# car1.net
KiCad netlist of a schematic drawn in EAGLE
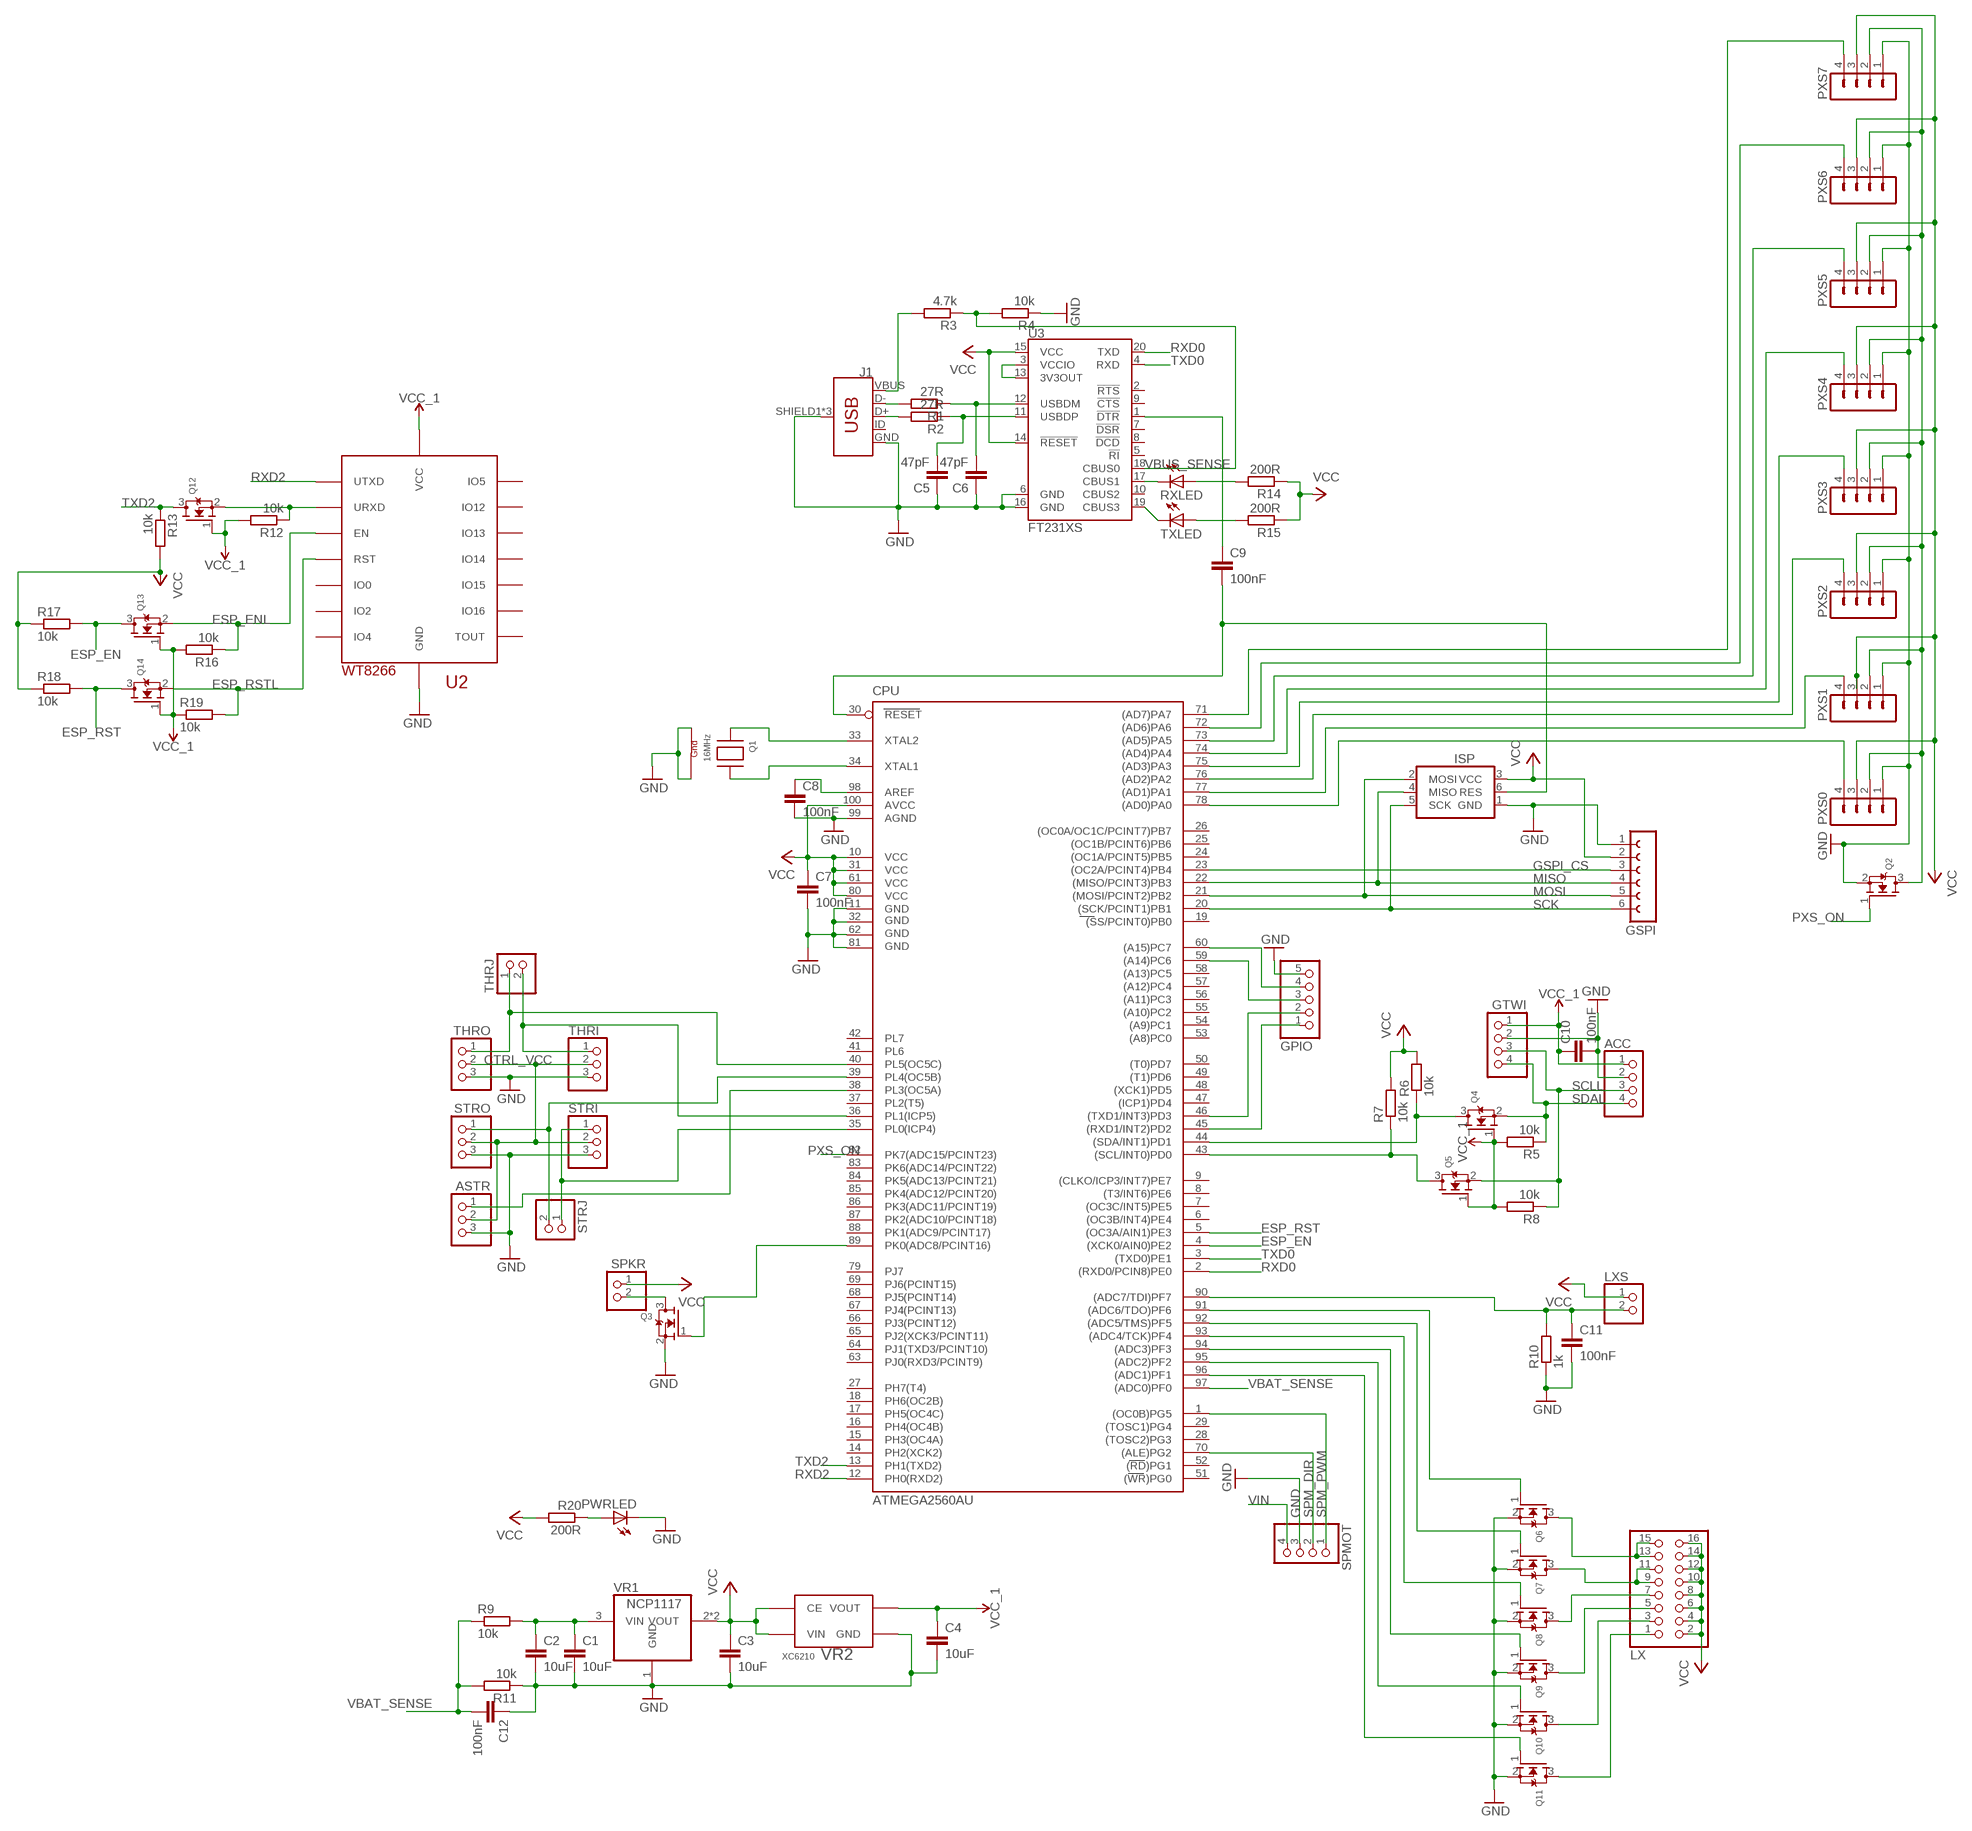
[diagram p0: schematic, sheet 1]

(export (version "E")
  (design (tool "Eeschema 10.0.6"))
  (components
    (comp (ref "ACC")
      (value "PINHD-1X4")
      (footprint "eagle-import:1X04")
      (libsource (lib "eagle-import") (part "PINHD-1X4"))
    )
    (comp (ref "ASTR")
      (value "PINHD-1X3")
      (footprint "eagle-import:1X03")
      (libsource (lib "eagle-import") (part "PINHD-1X3"))
    )
    (comp (ref "C1")
      (value "10uF")
      (footprint "eagle-import:C1206")
      (libsource (lib "eagle-import") (part "C-EUC1206"))
    )
    (comp (ref "C2")
      (value "10uF")
      (footprint "eagle-import:C1206")
      (libsource (lib "eagle-import") (part "C-EUC1206"))
    )
    (comp (ref "C3")
      (value "10uF")
      (footprint "eagle-import:C1206")
      (libsource (lib "eagle-import") (part "C-EUC1206"))
    )
    (comp (ref "C4")
      (value "10uF")
      (footprint "eagle-import:C1206")
      (libsource (lib "eagle-import") (part "C-EUC1206"))
    )
    (comp (ref "C5")
      (value "47pF")
      (footprint "eagle-import:C0603")
      (libsource (lib "eagle-import") (part "C-EUC0603"))
    )
    (comp (ref "C6")
      (value "47pF")
      (footprint "eagle-import:C0603")
      (libsource (lib "eagle-import") (part "C-EUC0603"))
    )
    (comp (ref "C7")
      (value "100nF")
      (footprint "eagle-import:C1206")
      (libsource (lib "eagle-import") (part "C-EUC1206"))
    )
    (comp (ref "C8")
      (value "100nF")
      (footprint "eagle-import:C1206")
      (libsource (lib "eagle-import") (part "C-EUC1206"))
    )
    (comp (ref "C9")
      (value "100nF")
      (footprint "eagle-import:C1206")
      (libsource (lib "eagle-import") (part "C-EUC1206"))
    )
    (comp (ref "C10")
      (value "100nF")
      (footprint "eagle-import:C1206")
      (libsource (lib "eagle-import") (part "C-EUC1206"))
    )
    (comp (ref "C11")
      (value "100nF")
      (footprint "eagle-import:C1206")
      (libsource (lib "eagle-import") (part "C-EUC1206"))
    )
    (comp (ref "C12")
      (value "100nF")
      (footprint "eagle-import:C1206")
      (libsource (lib "eagle-import") (part "C-EUC1206"))
    )
    (comp (ref "CPU")
      (value "ATMEGA2560AU")
      (footprint "eagle-import:TQFP100")
      (libsource (lib "eagle-import") (part "ATMEGA2560AU"))
    )
    (comp (ref "GPIO")
      (value "PINHD-1X5")
      (footprint "eagle-import:1X05")
      (libsource (lib "eagle-import") (part "PINHD-1X5"))
    )
    (comp (ref "GSPI")
      (value "FE06W")
      (footprint "eagle-import:FE06W")
      (libsource (lib "eagle-import") (part "FE06W"))
    )
    (comp (ref "GTWI")
      (value "PINHD-1X4/90")
      (footprint "eagle-import:1X04_90")
      (libsource (lib "eagle-import") (part "PINHD-1X4/90"))
    )
    (comp (ref "ISP")
      (value "ISP")
      (footprint "eagle-import:ISP")
      (libsource (lib "eagle-import") (part "ISP"))
    )
    (comp (ref "J1")
      (value "USB_MICRO-B_FEMALE-SMT")
      (footprint "eagle-import:USB-B-MICRO-SMD")
      (libsource (lib "eagle-import") (part "USB_MICRO-B_FEMALE-SMT"))
    )
    (comp (ref "LX")
      (value "PINHD-2X8")
      (footprint "eagle-import:2X08")
      (libsource (lib "eagle-import") (part "PINHD-2X8"))
    )
    (comp (ref "LXS")
      (value "PINHD-1X2")
      (footprint "eagle-import:1X02")
      (libsource (lib "eagle-import") (part "PINHD-1X2"))
    )
    (comp (ref "PWRLED")
      (value "LEDCHIP-LED0603")
      (footprint "eagle-import:CHIP-LED0603")
      (libsource (lib "eagle-import") (part "LEDCHIP-LED0603"))
    )
    (comp (ref "PXS0")
      (value "MA04-1")
      (footprint "eagle-import:MA04-1")
      (libsource (lib "eagle-import") (part "MA04-1"))
    )
    (comp (ref "PXS1")
      (value "MA04-1")
      (footprint "eagle-import:MA04-1")
      (libsource (lib "eagle-import") (part "MA04-1"))
    )
    (comp (ref "PXS2")
      (value "MA04-1")
      (footprint "eagle-import:MA04-1")
      (libsource (lib "eagle-import") (part "MA04-1"))
    )
    (comp (ref "PXS3")
      (value "MA04-1")
      (footprint "eagle-import:MA04-1")
      (libsource (lib "eagle-import") (part "MA04-1"))
    )
    (comp (ref "PXS4")
      (value "MA04-1")
      (footprint "eagle-import:MA04-1")
      (libsource (lib "eagle-import") (part "MA04-1"))
    )
    (comp (ref "PXS5")
      (value "MA04-1")
      (footprint "eagle-import:MA04-1")
      (libsource (lib "eagle-import") (part "MA04-1"))
    )
    (comp (ref "PXS6")
      (value "MA04-1")
      (footprint "eagle-import:MA04-1")
      (libsource (lib "eagle-import") (part "MA04-1"))
    )
    (comp (ref "PXS7")
      (value "MA04-1")
      (footprint "eagle-import:MA04-1")
      (libsource (lib "eagle-import") (part "MA04-1"))
    )
    (comp (ref "Q1")
      (value "16MHz")
      (footprint "eagle-import:NX3225")
      (libsource (lib "eagle-import") (part "XTAL-4-3225"))
    )
    (comp (ref "Q2")
      (value "MOSFET-NREFLOW")
      (footprint "eagle-import:SOT23")
      (libsource (lib "eagle-import") (part "MOSFET-NREFLOW"))
    )
    (comp (ref "Q3")
      (value "MOSFET-NREFLOW")
      (footprint "eagle-import:SOT23")
      (libsource (lib "eagle-import") (part "MOSFET-NREFLOW"))
    )
    (comp (ref "Q4")
      (value "MOSFET-NREFLOW")
      (footprint "eagle-import:SOT23")
      (libsource (lib "eagle-import") (part "MOSFET-NREFLOW"))
    )
    (comp (ref "Q5")
      (value "MOSFET-NREFLOW")
      (footprint "eagle-import:SOT23")
      (libsource (lib "eagle-import") (part "MOSFET-NREFLOW"))
    )
    (comp (ref "Q6")
      (value "MOSFET-NREFLOW")
      (footprint "eagle-import:SOT23")
      (libsource (lib "eagle-import") (part "MOSFET-NREFLOW"))
    )
    (comp (ref "Q7")
      (value "MOSFET-NREFLOW")
      (footprint "eagle-import:SOT23")
      (libsource (lib "eagle-import") (part "MOSFET-NREFLOW"))
    )
    (comp (ref "Q8")
      (value "MOSFET-NREFLOW")
      (footprint "eagle-import:SOT23")
      (libsource (lib "eagle-import") (part "MOSFET-NREFLOW"))
    )
    (comp (ref "Q9")
      (value "MOSFET-NREFLOW")
      (footprint "eagle-import:SOT23")
      (libsource (lib "eagle-import") (part "MOSFET-NREFLOW"))
    )
    (comp (ref "Q10")
      (value "MOSFET-NREFLOW")
      (footprint "eagle-import:SOT23")
      (libsource (lib "eagle-import") (part "MOSFET-NREFLOW"))
    )
    (comp (ref "Q11")
      (value "MOSFET-NREFLOW")
      (footprint "eagle-import:SOT23")
      (libsource (lib "eagle-import") (part "MOSFET-NREFLOW"))
    )
    (comp (ref "Q12")
      (value "MOSFET-NREFLOW")
      (footprint "eagle-import:SOT23")
      (libsource (lib "eagle-import") (part "MOSFET-NREFLOW"))
    )
    (comp (ref "Q13")
      (value "MOSFET-NREFLOW")
      (footprint "eagle-import:SOT23")
      (libsource (lib "eagle-import") (part "MOSFET-NREFLOW"))
    )
    (comp (ref "Q14")
      (value "MOSFET-NREFLOW")
      (footprint "eagle-import:SOT23")
      (libsource (lib "eagle-import") (part "MOSFET-NREFLOW"))
    )
    (comp (ref "R1")
      (value "27R")
      (footprint "eagle-import:R0603")
      (libsource (lib "eagle-import") (part "R-EU_R0603"))
    )
    (comp (ref "R2")
      (value "27R")
      (footprint "eagle-import:R0603")
      (libsource (lib "eagle-import") (part "R-EU_R0603"))
    )
    (comp (ref "R3")
      (value "4.7k")
      (footprint "eagle-import:R0603")
      (libsource (lib "eagle-import") (part "R-EU_R0603"))
    )
    (comp (ref "R4")
      (value "10k")
      (footprint "eagle-import:R0603")
      (libsource (lib "eagle-import") (part "R-EU_R0603"))
    )
    (comp (ref "R5")
      (value "10k")
      (footprint "eagle-import:R0603")
      (libsource (lib "eagle-import") (part "R-EU_R0603"))
    )
    (comp (ref "R6")
      (value "10k")
      (footprint "eagle-import:R0603")
      (libsource (lib "eagle-import") (part "R-EU_R0603"))
    )
    (comp (ref "R7")
      (value "10k")
      (footprint "eagle-import:R0603")
      (libsource (lib "eagle-import") (part "R-EU_R0603"))
    )
    (comp (ref "R8")
      (value "10k")
      (footprint "eagle-import:R0603")
      (libsource (lib "eagle-import") (part "R-EU_R0603"))
    )
    (comp (ref "R9")
      (value "10k")
      (footprint "eagle-import:R0805")
      (libsource (lib "eagle-import") (part "R-EU_R0805"))
    )
    (comp (ref "R10")
      (value "1k")
      (footprint "eagle-import:R0603")
      (libsource (lib "eagle-import") (part "R-EU_R0603"))
    )
    (comp (ref "R11")
      (value "10k")
      (footprint "eagle-import:R0805")
      (libsource (lib "eagle-import") (part "R-EU_R0805"))
    )
    (comp (ref "R12")
      (value "10k")
      (footprint "eagle-import:R0603")
      (libsource (lib "eagle-import") (part "R-EU_R0603"))
    )
    (comp (ref "R13")
      (value "10k")
      (footprint "eagle-import:R0603")
      (libsource (lib "eagle-import") (part "R-EU_R0603"))
    )
    (comp (ref "R14")
      (value "200R")
      (footprint "eagle-import:R0603")
      (libsource (lib "eagle-import") (part "R-EU_R0603"))
    )
    (comp (ref "R15")
      (value "200R")
      (footprint "eagle-import:R0603")
      (libsource (lib "eagle-import") (part "R-EU_R0603"))
    )
    (comp (ref "R16")
      (value "10k")
      (footprint "eagle-import:R0603")
      (libsource (lib "eagle-import") (part "R-EU_R0603"))
    )
    (comp (ref "R17")
      (value "10k")
      (footprint "eagle-import:R0603")
      (libsource (lib "eagle-import") (part "R-EU_R0603"))
    )
    (comp (ref "R18")
      (value "10k")
      (footprint "eagle-import:R0603")
      (libsource (lib "eagle-import") (part "R-EU_R0603"))
    )
    (comp (ref "R19")
      (value "10k")
      (footprint "eagle-import:R0603")
      (libsource (lib "eagle-import") (part "R-EU_R0603"))
    )
    (comp (ref "R20")
      (value "200R")
      (footprint "eagle-import:R0603")
      (libsource (lib "eagle-import") (part "R-EU_R0603"))
    )
    (comp (ref "RXLED")
      (value "LEDCHIP-LED0603")
      (footprint "eagle-import:CHIP-LED0603")
      (libsource (lib "eagle-import") (part "LEDCHIP-LED0603"))
    )
    (comp (ref "SPKR")
      (value "PINHD-1X2")
      (footprint "eagle-import:1X02")
      (libsource (lib "eagle-import") (part "PINHD-1X2"))
    )
    (comp (ref "SPMOT")
      (value "PINHD-1X4/90")
      (footprint "eagle-import:1X04_90")
      (libsource (lib "eagle-import") (part "PINHD-1X4/90"))
    )
    (comp (ref "STRI")
      (value "PINHD-1X3")
      (footprint "eagle-import:1X03")
      (libsource (lib "eagle-import") (part "PINHD-1X3"))
    )
    (comp (ref "STRJ")
      (value "PINHD-1X2")
      (footprint "eagle-import:1X02")
      (libsource (lib "eagle-import") (part "PINHD-1X2"))
    )
    (comp (ref "STRO")
      (value "PINHD-1X3")
      (footprint "eagle-import:1X03")
      (libsource (lib "eagle-import") (part "PINHD-1X3"))
    )
    (comp (ref "THRI")
      (value "PINHD-1X3")
      (footprint "eagle-import:1X03")
      (libsource (lib "eagle-import") (part "PINHD-1X3"))
    )
    (comp (ref "THRJ")
      (value "PINHD-1X2")
      (footprint "eagle-import:1X02")
      (libsource (lib "eagle-import") (part "PINHD-1X2"))
    )
    (comp (ref "THRO")
      (value "PINHD-1X3")
      (footprint "eagle-import:1X03")
      (libsource (lib "eagle-import") (part "PINHD-1X3"))
    )
    (comp (ref "TXLED")
      (value "LEDCHIP-LED0603")
      (footprint "eagle-import:CHIP-LED0603")
      (libsource (lib "eagle-import") (part "LEDCHIP-LED0603"))
    )
    (comp (ref "U2")
      (value "WT8266")
      (footprint "eagle-import:WT8266")
      (libsource (lib "eagle-import") (part "WT8266"))
    )
    (comp (ref "U3")
      (value "FT231XS")
      (footprint "eagle-import:SSOP20_L")
      (libsource (lib "eagle-import") (part "FT231XS"))
    )
    (comp (ref "VR1")
      (value "NCP1117")
      (footprint "eagle-import:SOT223")
      (fields (field (name "MPN") "REG1117"))
      (libsource (lib "eagle-import") (part "REG1117"))
    )
    (comp (ref "VR2")
      (value "XC6210")
      (footprint "eagle-import:SOT25")
      (libsource (lib "eagle-import") (part "XC6210"))
    )
  )
  (nets
    (net (code "1") (name "/CTRL_VCC") (class "Default")
      (node (ref "ASTR") (pin "2") (pinfunction "2_2") (pintype "passive"))
      (node (ref "STRI") (pin "2") (pinfunction "2_2") (pintype "passive"))
      (node (ref "STRO") (pin "2") (pinfunction "2_2") (pintype "passive"))
      (node (ref "THRI") (pin "2") (pinfunction "2_2") (pintype "passive"))
      (node (ref "THRO") (pin "2") (pinfunction "2_2") (pintype "passive"))
    )
    (net (code "2") (name "/ESP_EN") (class "Default")
      (node (ref "CPU") (pin "4") (pinfunction "(XCK0/AIN0)PE2_4") (pintype "bidirectional"))
      (node (ref "Q13") (pin "3") (pinfunction "D_3") (pintype "bidirectional"))
      (node (ref "R17") (pin "2") (pinfunction "2_2") (pintype "passive"))
    )
    (net (code "3") (name "/ESP_ENL") (class "Default")
      (node (ref "Q13") (pin "2") (pinfunction "S_2") (pintype "bidirectional"))
      (node (ref "R16") (pin "1") (pinfunction "1_1") (pintype "passive"))
      (node (ref "U2") (pin "EN") (pinfunction "EN_EN") (pintype "bidirectional"))
    )
    (net (code "4") (name "/ESP_RST") (class "Default")
      (node (ref "CPU") (pin "5") (pinfunction "(OC3A/AIN1)PE3_5") (pintype "bidirectional"))
      (node (ref "Q14") (pin "3") (pinfunction "D_3") (pintype "bidirectional"))
      (node (ref "R18") (pin "2") (pinfunction "2_2") (pintype "passive"))
    )
    (net (code "5") (name "/ESP_RSTL") (class "Default")
      (node (ref "Q14") (pin "2") (pinfunction "S_2") (pintype "bidirectional"))
      (node (ref "R19") (pin "2") (pinfunction "2_2") (pintype "passive"))
      (node (ref "U2") (pin "RST") (pinfunction "RST_RST") (pintype "bidirectional"))
    )
    (net (code "6") (name "/GSPI_CS") (class "Default")
      (node (ref "CPU") (pin "23") (pinfunction "(OC2A/PCINT4)PB4_23") (pintype "bidirectional"))
      (node (ref "GSPI") (pin "3") (pinfunction "3_3") (pintype "passive"))
    )
    (net (code "7") (name "/MISO") (class "Default")
      (node (ref "CPU") (pin "22") (pinfunction "(MISO/PCINT3)PB3_22") (pintype "bidirectional"))
      (node (ref "GSPI") (pin "4") (pinfunction "4_4") (pintype "passive"))
      (node (ref "ISP") (pin "4") (pinfunction "MISO_4") (pintype "bidirectional"))
    )
    (net (code "8") (name "/MOSI") (class "Default")
      (node (ref "CPU") (pin "21") (pinfunction "(MOSI/PCINT2)PB2_21") (pintype "bidirectional"))
      (node (ref "GSPI") (pin "5") (pinfunction "5_5") (pintype "passive"))
      (node (ref "ISP") (pin "2") (pinfunction "MOSI_2") (pintype "bidirectional"))
    )
    (net (code "9") (name "/PXS_ON") (class "Default")
      (node (ref "CPU") (pin "82") (pinfunction "PK7(ADC15/PCINT23)_82") (pintype "bidirectional"))
      (node (ref "Q2") (pin "1") (pinfunction "G_1") (pintype "bidirectional"))
    )
    (net (code "10") (name "/RXD0") (class "Default")
      (node (ref "CPU") (pin "2") (pinfunction "(RXD0/PCIN8)PE0_2") (pintype "bidirectional"))
      (node (ref "U3") (pin "20") (pinfunction "TXD_20") (pintype "bidirectional"))
    )
    (net (code "11") (name "/RXD2") (class "Default")
      (node (ref "CPU") (pin "12") (pinfunction "PH0(RXD2)_12") (pintype "bidirectional"))
      (node (ref "U2") (pin "UTXD") (pinfunction "UTXD_UTXD") (pintype "bidirectional"))
    )
    (net (code "12") (name "/SCK") (class "Default")
      (node (ref "CPU") (pin "20") (pinfunction "(SCK/PCINT1)PB1_20") (pintype "bidirectional"))
      (node (ref "GSPI") (pin "6") (pinfunction "6_6") (pintype "passive"))
      (node (ref "ISP") (pin "5") (pinfunction "SCK_5") (pintype "bidirectional"))
    )
    (net (code "13") (name "/SCLL") (class "Default")
      (node (ref "ACC") (pin "3") (pinfunction "3_3") (pintype "passive"))
      (node (ref "GTWI") (pin "3") (pinfunction "3_3") (pintype "passive"))
      (node (ref "Q5") (pin "2") (pinfunction "S_2") (pintype "bidirectional"))
      (node (ref "R8") (pin "1") (pinfunction "1_1") (pintype "passive"))
    )
    (net (code "14") (name "/SDAL") (class "Default")
      (node (ref "ACC") (pin "4") (pinfunction "4_4") (pintype "passive"))
      (node (ref "GTWI") (pin "4") (pinfunction "4_4") (pintype "passive"))
      (node (ref "Q4") (pin "2") (pinfunction "S_2") (pintype "bidirectional"))
      (node (ref "R5") (pin "1") (pinfunction "1_1") (pintype "passive"))
    )
    (net (code "15") (name "/SPM_DIR") (class "Default")
      (node (ref "CPU") (pin "70") (pinfunction "(ALE)PG2_70") (pintype "bidirectional"))
      (node (ref "SPMOT") (pin "2") (pinfunction "2_2") (pintype "passive"))
    )
    (net (code "16") (name "/SPM_PWM") (class "Default")
      (node (ref "CPU") (pin "1") (pinfunction "(OC0B)PG5_1") (pintype "bidirectional"))
      (node (ref "SPMOT") (pin "1") (pinfunction "1_1") (pintype "passive"))
    )
    (net (code "17") (name "/TXD0") (class "Default")
      (node (ref "CPU") (pin "3") (pinfunction "(TXD0)PE1_3") (pintype "bidirectional"))
      (node (ref "U3") (pin "4") (pinfunction "RXD_4") (pintype "bidirectional"))
    )
    (net (code "18") (name "/TXD2") (class "Default")
      (node (ref "CPU") (pin "13") (pinfunction "PH1(TXD2)_13") (pintype "bidirectional"))
      (node (ref "Q12") (pin "3") (pinfunction "D_3") (pintype "bidirectional"))
      (node (ref "R13") (pin "1") (pinfunction "1_1") (pintype "passive"))
    )
    (net (code "19") (name "/VBAT_SENSE") (class "Default")
      (node (ref "C12") (pin "2") (pinfunction "2_2") (pintype "passive"))
      (node (ref "CPU") (pin "97") (pinfunction "(ADC0)PF0_97") (pintype "bidirectional"))
      (node (ref "R11") (pin "2") (pinfunction "2_2") (pintype "passive"))
      (node (ref "R9") (pin "1") (pinfunction "1_1") (pintype "passive"))
    )
    (net (code "20") (name "/VBUS_SENSE") (class "Default")
      (node (ref "R3") (pin "1") (pinfunction "1_1") (pintype "passive"))
      (node (ref "R4") (pin "2") (pinfunction "2_2") (pintype "passive"))
      (node (ref "U3") (pin "18") (pinfunction "CBUS0_18") (pintype "bidirectional"))
    )
    (net (code "21") (name "/VIN") (class "Default")
      (node (ref "C1") (pin "1") (pinfunction "1_1") (pintype "passive"))
      (node (ref "C2") (pin "1") (pinfunction "1_1") (pintype "passive"))
      (node (ref "R9") (pin "2") (pinfunction "2_2") (pintype "passive"))
      (node (ref "SPMOT") (pin "4") (pinfunction "4_4") (pintype "passive"))
      (node (ref "VR1") (pin "3") (pinfunction "VIN_3") (pintype "input"))
    )
    (net (code "22") (name "GND") (class "Default")
      (node (ref "ACC") (pin "2") (pinfunction "2_2") (pintype "passive"))
      (node (ref "ASTR") (pin "3") (pinfunction "3_3") (pintype "passive"))
      (node (ref "C1") (pin "2") (pinfunction "2_2") (pintype "passive"))
      (node (ref "C10") (pin "2") (pinfunction "2_2") (pintype "passive"))
      (node (ref "C11") (pin "2") (pinfunction "2_2") (pintype "passive"))
      (node (ref "C12") (pin "1") (pinfunction "1_1") (pintype "passive"))
      (node (ref "C2") (pin "2") (pinfunction "2_2") (pintype "passive"))
      (node (ref "C3") (pin "2") (pinfunction "2_2") (pintype "passive"))
      (node (ref "C4") (pin "2") (pinfunction "2_2") (pintype "passive"))
      (node (ref "C5") (pin "1") (pinfunction "1_1") (pintype "passive"))
      (node (ref "C6") (pin "1") (pinfunction "1_1") (pintype "passive"))
      (node (ref "C7") (pin "2") (pinfunction "2_2") (pintype "passive"))
      (node (ref "C8") (pin "2") (pinfunction "2_2") (pintype "passive"))
      (node (ref "CPU") (pin "11") (pinfunction "GND_11") (pintype "power_in"))
      (node (ref "CPU") (pin "32") (pinfunction "GND1_32") (pintype "power_in"))
      (node (ref "CPU") (pin "62") (pinfunction "GND2_62") (pintype "power_in"))
      (node (ref "CPU") (pin "81") (pinfunction "GND3_81") (pintype "power_in"))
      (node (ref "CPU") (pin "99") (pinfunction "AGND_99") (pintype "power_in"))
      (node (ref "GPIO") (pin "5") (pinfunction "5_5") (pintype "passive"))
      (node (ref "GSPI") (pin "1") (pinfunction "1_1") (pintype "passive"))
      (node (ref "GTWI") (pin "2") (pinfunction "2_2") (pintype "passive"))
      (node (ref "ISP") (pin "1") (pinfunction "GND_1") (pintype "bidirectional"))
      (node (ref "J1") (pin "GND") (pinfunction "GND_GND") (pintype "power_in"))
      (node (ref "J1") (pin "SHIELD1") (pinfunction "SHIELD_SHIELD1") (pintype "bidirectional"))
      (node (ref "J1") (pin "SHIELD2") (pinfunction "SHIELD_SHIELD2") (pintype "bidirectional"))
      (node (ref "J1") (pin "SHIELD3") (pinfunction "SHIELD_SHIELD3") (pintype "bidirectional"))
      (node (ref "PWRLED") (pin "C") (pinfunction "C_C") (pintype "passive"))
      (node (ref "PXS0") (pin "1") (pinfunction "1_1") (pintype "passive"))
      (node (ref "PXS1") (pin "1") (pinfunction "1_1") (pintype "passive"))
      (node (ref "PXS2") (pin "1") (pinfunction "1_1") (pintype "passive"))
      (node (ref "PXS3") (pin "1") (pinfunction "1_1") (pintype "passive"))
      (node (ref "PXS4") (pin "1") (pinfunction "1_1") (pintype "passive"))
      (node (ref "PXS5") (pin "1") (pinfunction "1_1") (pintype "passive"))
      (node (ref "PXS6") (pin "1") (pinfunction "1_1") (pintype "passive"))
      (node (ref "PXS7") (pin "1") (pinfunction "1_1") (pintype "passive"))
      (node (ref "Q1") (pin "2") (pinfunction "G2_2") (pintype "power_in"))
      (node (ref "Q1") (pin "4") (pinfunction "G1_4") (pintype "power_in"))
      (node (ref "Q10") (pin "2") (pinfunction "S_2") (pintype "bidirectional"))
      (node (ref "Q11") (pin "2") (pinfunction "S_2") (pintype "bidirectional"))
      (node (ref "Q2") (pin "2") (pinfunction "S_2") (pintype "bidirectional"))
      (node (ref "Q3") (pin "2") (pinfunction "S_2") (pintype "bidirectional"))
      (node (ref "Q6") (pin "2") (pinfunction "S_2") (pintype "bidirectional"))
      (node (ref "Q7") (pin "2") (pinfunction "S_2") (pintype "bidirectional"))
      (node (ref "Q8") (pin "2") (pinfunction "S_2") (pintype "bidirectional"))
      (node (ref "Q9") (pin "2") (pinfunction "S_2") (pintype "bidirectional"))
      (node (ref "R10") (pin "1") (pinfunction "1_1") (pintype "passive"))
      (node (ref "R11") (pin "1") (pinfunction "1_1") (pintype "passive"))
      (node (ref "R4") (pin "1") (pinfunction "1_1") (pintype "passive"))
      (node (ref "SPMOT") (pin "3") (pinfunction "3_3") (pintype "passive"))
      (node (ref "STRI") (pin "3") (pinfunction "3_3") (pintype "passive"))
      (node (ref "STRO") (pin "3") (pinfunction "3_3") (pintype "passive"))
      (node (ref "THRI") (pin "3") (pinfunction "3_3") (pintype "passive"))
      (node (ref "THRO") (pin "3") (pinfunction "3_3") (pintype "passive"))
      (node (ref "U2") (pin "GND0") (pinfunction "GND_GND0") (pintype "power_in"))
      (node (ref "U2") (pin "GND1") (pinfunction "GND_GND1") (pintype "power_in"))
      (node (ref "U2") (pin "GND2") (pinfunction "GND_GND2") (pintype "power_in"))
      (node (ref "U3") (pin "16") (pinfunction "GND_16") (pintype "bidirectional"))
      (node (ref "U3") (pin "6") (pinfunction "GND_6") (pintype "bidirectional"))
      (node (ref "VR1") (pin "1") (pinfunction "GND_1") (pintype "power_in"))
      (node (ref "VR2") (pin "2") (pinfunction "GND_2") (pintype "power_in"))
    )
    (net (code "23") (name "Net-(CPU-(A14)PC6)") (class "Default")
      (node (ref "CPU") (pin "59") (pinfunction "(A14)PC6_59") (pintype "bidirectional"))
      (node (ref "GPIO") (pin "3") (pinfunction "3_3") (pintype "passive"))
    )
    (net (code "24") (name "Net-(CPU-(A15)PC7)") (class "Default")
      (node (ref "CPU") (pin "60") (pinfunction "(A15)PC7_60") (pintype "bidirectional"))
      (node (ref "GPIO") (pin "4") (pinfunction "4_4") (pintype "passive"))
    )
    (net (code "25") (name "Net-(CPU-(AD0)PA0)") (class "Default")
      (node (ref "CPU") (pin "78") (pinfunction "(AD0)PA0_78") (pintype "bidirectional"))
      (node (ref "PXS0") (pin "4") (pinfunction "4_4") (pintype "passive"))
    )
    (net (code "26") (name "Net-(CPU-(AD1)PA1)") (class "Default")
      (node (ref "CPU") (pin "77") (pinfunction "(AD1)PA1_77") (pintype "bidirectional"))
      (node (ref "PXS1") (pin "4") (pinfunction "4_4") (pintype "passive"))
    )
    (net (code "27") (name "Net-(CPU-(AD2)PA2)") (class "Default")
      (node (ref "CPU") (pin "76") (pinfunction "(AD2)PA2_76") (pintype "bidirectional"))
      (node (ref "PXS2") (pin "4") (pinfunction "4_4") (pintype "passive"))
    )
    (net (code "28") (name "Net-(CPU-(AD3)PA3)") (class "Default")
      (node (ref "CPU") (pin "75") (pinfunction "(AD3)PA3_75") (pintype "bidirectional"))
      (node (ref "PXS3") (pin "4") (pinfunction "4_4") (pintype "passive"))
    )
    (net (code "29") (name "Net-(CPU-(AD4)PA4)") (class "Default")
      (node (ref "CPU") (pin "74") (pinfunction "(AD4)PA4_74") (pintype "bidirectional"))
      (node (ref "PXS4") (pin "4") (pinfunction "4_4") (pintype "passive"))
    )
    (net (code "30") (name "Net-(CPU-(AD5)PA5)") (class "Default")
      (node (ref "CPU") (pin "73") (pinfunction "(AD5)PA5_73") (pintype "bidirectional"))
      (node (ref "PXS5") (pin "4") (pinfunction "4_4") (pintype "passive"))
    )
    (net (code "31") (name "Net-(CPU-(AD6)PA6)") (class "Default")
      (node (ref "CPU") (pin "72") (pinfunction "(AD6)PA6_72") (pintype "bidirectional"))
      (node (ref "PXS6") (pin "4") (pinfunction "4_4") (pintype "passive"))
    )
    (net (code "32") (name "Net-(CPU-(AD7)PA7)") (class "Default")
      (node (ref "CPU") (pin "71") (pinfunction "(AD7)PA7_71") (pintype "bidirectional"))
      (node (ref "PXS7") (pin "4") (pinfunction "4_4") (pintype "passive"))
    )
    (net (code "33") (name "Net-(CPU-(ADC1)PF1)") (class "Default")
      (node (ref "CPU") (pin "96") (pinfunction "(ADC1)PF1_96") (pintype "bidirectional"))
      (node (ref "Q11") (pin "1") (pinfunction "G_1") (pintype "bidirectional"))
    )
    (net (code "34") (name "Net-(CPU-(ADC2)PF2)") (class "Default")
      (node (ref "CPU") (pin "95") (pinfunction "(ADC2)PF2_95") (pintype "bidirectional"))
      (node (ref "Q10") (pin "1") (pinfunction "G_1") (pintype "bidirectional"))
    )
    (net (code "35") (name "Net-(CPU-(ADC3)PF3)") (class "Default")
      (node (ref "CPU") (pin "94") (pinfunction "(ADC3)PF3_94") (pintype "bidirectional"))
      (node (ref "Q9") (pin "1") (pinfunction "G_1") (pintype "bidirectional"))
    )
    (net (code "36") (name "Net-(CPU-(ADC4{slash}TCK)PF4)") (class "Default")
      (node (ref "CPU") (pin "93") (pinfunction "(ADC4/TCK)PF4_93") (pintype "bidirectional"))
      (node (ref "Q8") (pin "1") (pinfunction "G_1") (pintype "bidirectional"))
    )
    (net (code "37") (name "Net-(CPU-(ADC5{slash}TMS)PF5)") (class "Default")
      (node (ref "CPU") (pin "92") (pinfunction "(ADC5/TMS)PF5_92") (pintype "bidirectional"))
      (node (ref "Q7") (pin "1") (pinfunction "G_1") (pintype "bidirectional"))
    )
    (net (code "38") (name "Net-(CPU-(ADC6{slash}TDO)PF6)") (class "Default")
      (node (ref "CPU") (pin "91") (pinfunction "(ADC6/TDO)PF6_91") (pintype "bidirectional"))
      (node (ref "Q6") (pin "1") (pinfunction "G_1") (pintype "bidirectional"))
    )
    (net (code "39") (name "Net-(CPU-(ADC7{slash}TDI)PF7)") (class "Default")
      (node (ref "C11") (pin "1") (pinfunction "1_1") (pintype "passive"))
      (node (ref "CPU") (pin "90") (pinfunction "(ADC7/TDI)PF7_90") (pintype "bidirectional"))
      (node (ref "LXS") (pin "2") (pinfunction "2_2") (pintype "passive"))
      (node (ref "R10") (pin "2") (pinfunction "2_2") (pintype "passive"))
    )
    (net (code "40") (name "Net-(CPU-(RXD1{slash}INT2)PD2)") (class "Default")
      (node (ref "CPU") (pin "45") (pinfunction "(RXD1/INT2)PD2_45") (pintype "bidirectional"))
      (node (ref "GPIO") (pin "1") (pinfunction "1_1") (pintype "passive"))
    )
    (net (code "41") (name "Net-(CPU-(SCL{slash}INT0)PD0)") (class "Default")
      (node (ref "CPU") (pin "43") (pinfunction "(SCL/INT0)PD0_43") (pintype "bidirectional"))
      (node (ref "Q5") (pin "3") (pinfunction "D_3") (pintype "bidirectional"))
      (node (ref "R7") (pin "1") (pinfunction "1_1") (pintype "passive"))
    )
    (net (code "42") (name "Net-(CPU-(SDA{slash}INT1)PD1)") (class "Default")
      (node (ref "CPU") (pin "44") (pinfunction "(SDA/INT1)PD1_44") (pintype "bidirectional"))
      (node (ref "Q4") (pin "3") (pinfunction "D_3") (pintype "bidirectional"))
      (node (ref "R6") (pin "1") (pinfunction "1_1") (pintype "passive"))
    )
    (net (code "43") (name "Net-(CPU-(TXD1{slash}INT3)PD3)") (class "Default")
      (node (ref "CPU") (pin "46") (pinfunction "(TXD1/INT3)PD3_46") (pintype "bidirectional"))
      (node (ref "GPIO") (pin "2") (pinfunction "2_2") (pintype "passive"))
    )
    (net (code "44") (name "Net-(CPU-AREF)") (class "Default")
      (node (ref "C8") (pin "1") (pinfunction "1_1") (pintype "passive"))
      (node (ref "CPU") (pin "98") (pinfunction "AREF_98") (pintype "bidirectional"))
    )
    (net (code "45") (name "Net-(CPU-PK0(ADC8{slash}PCINT16))") (class "Default")
      (node (ref "CPU") (pin "89") (pinfunction "PK0(ADC8/PCINT16)_89") (pintype "bidirectional"))
      (node (ref "Q3") (pin "1") (pinfunction "G_1") (pintype "bidirectional"))
    )
    (net (code "46") (name "Net-(CPU-PL0(ICP4))") (class "Default")
      (node (ref "CPU") (pin "35") (pinfunction "PL0(ICP4)_35") (pintype "bidirectional"))
      (node (ref "STRI") (pin "1") (pinfunction "1_1") (pintype "passive"))
      (node (ref "STRJ") (pin "1") (pinfunction "1_1") (pintype "passive"))
    )
    (net (code "47") (name "Net-(CPU-PL1(ICP5))") (class "Default")
      (node (ref "CPU") (pin "36") (pinfunction "PL1(ICP5)_36") (pintype "bidirectional"))
      (node (ref "THRI") (pin "1") (pinfunction "1_1") (pintype "passive"))
      (node (ref "THRJ") (pin "2") (pinfunction "2_2") (pintype "passive"))
    )
    (net (code "48") (name "Net-(CPU-PL3(OC5A))") (class "Default")
      (node (ref "ASTR") (pin "1") (pinfunction "1_1") (pintype "passive"))
      (node (ref "CPU") (pin "38") (pinfunction "PL3(OC5A)_38") (pintype "bidirectional"))
    )
    (net (code "49") (name "Net-(CPU-PL4(OC5B))") (class "Default")
      (node (ref "CPU") (pin "39") (pinfunction "PL4(OC5B)_39") (pintype "bidirectional"))
      (node (ref "STRJ") (pin "2") (pinfunction "2_2") (pintype "passive"))
      (node (ref "STRO") (pin "1") (pinfunction "1_1") (pintype "passive"))
    )
    (net (code "50") (name "Net-(CPU-PL5(OC5C))") (class "Default")
      (node (ref "CPU") (pin "40") (pinfunction "PL5(OC5C)_40") (pintype "bidirectional"))
      (node (ref "THRJ") (pin "1") (pinfunction "1_1") (pintype "passive"))
      (node (ref "THRO") (pin "1") (pinfunction "1_1") (pintype "passive"))
    )
    (net (code "51") (name "Net-(CPU-RESET)") (class "Default")
      (node (ref "C9") (pin "2") (pinfunction "2_2") (pintype "passive"))
      (node (ref "CPU") (pin "30") (pinfunction "RESET_30") (pintype "input"))
      (node (ref "ISP") (pin "6") (pinfunction "RES_6") (pintype "bidirectional"))
    )
    (net (code "52") (name "Net-(CPU-XTAL1)") (class "Default")
      (node (ref "CPU") (pin "34") (pinfunction "XTAL1_34") (pintype "input"))
      (node (ref "Q1") (pin "3") (pinfunction "X2_3") (pintype "bidirectional"))
    )
    (net (code "53") (name "Net-(CPU-XTAL2)") (class "Default")
      (node (ref "CPU") (pin "33") (pinfunction "XTAL2_33") (pintype "output"))
      (node (ref "Q1") (pin "1") (pinfunction "X1_1") (pintype "bidirectional"))
    )
    (net (code "54") (name "Net-(J1-PadD+)") (class "Default")
      (node (ref "J1") (pin "D+") (pinfunction "D+_D+") (pintype "bidirectional"))
      (node (ref "R2") (pin "2") (pinfunction "2_2") (pintype "passive"))
    )
    (net (code "55") (name "Net-(J1-PadD-)") (class "Default")
      (node (ref "J1") (pin "D-") (pinfunction "D-_D-") (pintype "bidirectional"))
      (node (ref "R1") (pin "2") (pinfunction "2_2") (pintype "passive"))
    )
    (net (code "56") (name "Net-(J1-PadVBUS)") (class "Default")
      (node (ref "J1") (pin "VBUS") (pinfunction "VBUS_VBUS") (pintype "power_in"))
      (node (ref "R3") (pin "2") (pinfunction "2_2") (pintype "passive"))
    )
    (net (code "57") (name "Net-(PWRLED-PadA)") (class "Default")
      (node (ref "PWRLED") (pin "A") (pinfunction "A_A") (pintype "passive"))
      (node (ref "R20") (pin "1") (pinfunction "1_1") (pintype "passive"))
    )
    (net (code "58") (name "Net-(Q2-D)") (class "Default")
      (node (ref "PXS0") (pin "2") (pinfunction "2_2") (pintype "passive"))
      (node (ref "PXS1") (pin "2") (pinfunction "2_2") (pintype "passive"))
      (node (ref "PXS2") (pin "2") (pinfunction "2_2") (pintype "passive"))
      (node (ref "PXS3") (pin "2") (pinfunction "2_2") (pintype "passive"))
      (node (ref "PXS4") (pin "2") (pinfunction "2_2") (pintype "passive"))
      (node (ref "PXS5") (pin "2") (pinfunction "2_2") (pintype "passive"))
      (node (ref "PXS6") (pin "2") (pinfunction "2_2") (pintype "passive"))
      (node (ref "PXS7") (pin "2") (pinfunction "2_2") (pintype "passive"))
      (node (ref "Q2") (pin "3") (pinfunction "D_3") (pintype "bidirectional"))
    )
    (net (code "59") (name "Net-(Q3-D)") (class "Default")
      (node (ref "Q3") (pin "3") (pinfunction "D_3") (pintype "bidirectional"))
      (node (ref "SPKR") (pin "2") (pinfunction "2_2") (pintype "passive"))
    )
    (net (code "60") (name "Net-(Q6-D)") (class "Default")
      (node (ref "LX") (pin "13") (pinfunction "13_13") (pintype "passive"))
      (node (ref "LX") (pin "15") (pinfunction "15_15") (pintype "passive"))
      (node (ref "Q6") (pin "3") (pinfunction "D_3") (pintype "bidirectional"))
    )
    (net (code "61") (name "Net-(Q7-D)") (class "Default")
      (node (ref "LX") (pin "11") (pinfunction "11_11") (pintype "passive"))
      (node (ref "LX") (pin "9") (pinfunction "9_9") (pintype "passive"))
      (node (ref "Q7") (pin "3") (pinfunction "D_3") (pintype "bidirectional"))
    )
    (net (code "62") (name "Net-(Q8-D)") (class "Default")
      (node (ref "LX") (pin "7") (pinfunction "7_7") (pintype "passive"))
      (node (ref "Q8") (pin "3") (pinfunction "D_3") (pintype "bidirectional"))
    )
    (net (code "63") (name "Net-(Q9-D)") (class "Default")
      (node (ref "LX") (pin "5") (pinfunction "5_5") (pintype "passive"))
      (node (ref "Q9") (pin "3") (pinfunction "D_3") (pintype "bidirectional"))
    )
    (net (code "64") (name "Net-(Q10-D)") (class "Default")
      (node (ref "LX") (pin "3") (pinfunction "3_3") (pintype "passive"))
      (node (ref "Q10") (pin "3") (pinfunction "D_3") (pintype "bidirectional"))
    )
    (net (code "65") (name "Net-(Q11-D)") (class "Default")
      (node (ref "LX") (pin "1") (pinfunction "1_1") (pintype "passive"))
      (node (ref "Q11") (pin "3") (pinfunction "D_3") (pintype "bidirectional"))
    )
    (net (code "66") (name "Net-(Q12-S)") (class "Default")
      (node (ref "Q12") (pin "2") (pinfunction "S_2") (pintype "bidirectional"))
      (node (ref "R12") (pin "1") (pinfunction "1_1") (pintype "passive"))
      (node (ref "U2") (pin "URXD") (pinfunction "URXD_URXD") (pintype "bidirectional"))
    )
    (net (code "67") (name "Net-(R14-Pad2)") (class "Default")
      (node (ref "R14") (pin "2") (pinfunction "2_2") (pintype "passive"))
      (node (ref "RXLED") (pin "A") (pinfunction "A_A") (pintype "passive"))
    )
    (net (code "68") (name "Net-(R15-Pad2)") (class "Default")
      (node (ref "R15") (pin "2") (pinfunction "2_2") (pintype "passive"))
      (node (ref "TXLED") (pin "A") (pinfunction "A_A") (pintype "passive"))
    )
    (net (code "69") (name "Net-(U3-3V3OUT)") (class "Default")
      (node (ref "U3") (pin "13") (pinfunction "3V3OUT_13") (pintype "bidirectional"))
      (node (ref "U3") (pin "3") (pinfunction "VCCIO_3") (pintype "bidirectional"))
    )
    (net (code "70") (name "Net-(U3-CBUS1)") (class "Default")
      (node (ref "RXLED") (pin "C") (pinfunction "C_C") (pintype "passive"))
      (node (ref "U3") (pin "17") (pinfunction "CBUS1_17") (pintype "bidirectional"))
    )
    (net (code "71") (name "Net-(U3-CBUS3)") (class "Default")
      (node (ref "TXLED") (pin "C") (pinfunction "C_C") (pintype "passive"))
      (node (ref "U3") (pin "19") (pinfunction "CBUS3_19") (pintype "bidirectional"))
    )
    (net (code "72") (name "Net-(U3-USBDM)") (class "Default")
      (node (ref "C6") (pin "2") (pinfunction "2_2") (pintype "passive"))
      (node (ref "R1") (pin "1") (pinfunction "1_1") (pintype "passive"))
      (node (ref "U3") (pin "12") (pinfunction "USBDM_12") (pintype "bidirectional"))
    )
    (net (code "73") (name "Net-(U3-USBDP)") (class "Default")
      (node (ref "C5") (pin "2") (pinfunction "2_2") (pintype "passive"))
      (node (ref "R2") (pin "1") (pinfunction "1_1") (pintype "passive"))
      (node (ref "U3") (pin "11") (pinfunction "USBDP_11") (pintype "bidirectional"))
    )
    (net (code "74") (name "Net-(U3-~{DTR})") (class "Default")
      (node (ref "C9") (pin "1") (pinfunction "1_1") (pintype "passive"))
      (node (ref "U3") (pin "1") (pinfunction "~{DTR}_1") (pintype "bidirectional"))
    )
    (net (code "75") (name "VCC") (class "Default")
      (node (ref "C3") (pin "1") (pinfunction "1_1") (pintype "passive"))
      (node (ref "C7") (pin "1") (pinfunction "1_1") (pintype "passive"))
      (node (ref "CPU") (pin "10") (pinfunction "VCC_10") (pintype "power_in"))
      (node (ref "CPU") (pin "100") (pinfunction "AVCC_100") (pintype "power_in"))
      (node (ref "CPU") (pin "31") (pinfunction "VCC1_31") (pintype "power_in"))
      (node (ref "CPU") (pin "61") (pinfunction "VCC2_61") (pintype "power_in"))
      (node (ref "CPU") (pin "80") (pinfunction "VCC3_80") (pintype "power_in"))
      (node (ref "GSPI") (pin "2") (pinfunction "2_2") (pintype "passive"))
      (node (ref "ISP") (pin "3") (pinfunction "VCC_3") (pintype "bidirectional"))
      (node (ref "LX") (pin "10") (pinfunction "10_10") (pintype "passive"))
      (node (ref "LX") (pin "12") (pinfunction "12_12") (pintype "passive"))
      (node (ref "LX") (pin "14") (pinfunction "14_14") (pintype "passive"))
      (node (ref "LX") (pin "16") (pinfunction "16_16") (pintype "passive"))
      (node (ref "LX") (pin "2") (pinfunction "2_2") (pintype "passive"))
      (node (ref "LX") (pin "4") (pinfunction "4_4") (pintype "passive"))
      (node (ref "LX") (pin "6") (pinfunction "6_6") (pintype "passive"))
      (node (ref "LX") (pin "8") (pinfunction "8_8") (pintype "passive"))
      (node (ref "LXS") (pin "1") (pinfunction "1_1") (pintype "passive"))
      (node (ref "PXS0") (pin "3") (pinfunction "3_3") (pintype "passive"))
      (node (ref "PXS1") (pin "3") (pinfunction "3_3") (pintype "passive"))
      (node (ref "PXS2") (pin "3") (pinfunction "3_3") (pintype "passive"))
      (node (ref "PXS3") (pin "3") (pinfunction "3_3") (pintype "passive"))
      (node (ref "PXS4") (pin "3") (pinfunction "3_3") (pintype "passive"))
      (node (ref "PXS5") (pin "3") (pinfunction "3_3") (pintype "passive"))
      (node (ref "PXS6") (pin "3") (pinfunction "3_3") (pintype "passive"))
      (node (ref "PXS7") (pin "3") (pinfunction "3_3") (pintype "passive"))
      (node (ref "R13") (pin "2") (pinfunction "2_2") (pintype "passive"))
      (node (ref "R14") (pin "1") (pinfunction "1_1") (pintype "passive"))
      (node (ref "R15") (pin "1") (pinfunction "1_1") (pintype "passive"))
      (node (ref "R17") (pin "1") (pinfunction "1_1") (pintype "passive"))
      (node (ref "R18") (pin "1") (pinfunction "1_1") (pintype "passive"))
      (node (ref "R20") (pin "2") (pinfunction "2_2") (pintype "passive"))
      (node (ref "R6") (pin "2") (pinfunction "2_2") (pintype "passive"))
      (node (ref "R7") (pin "2") (pinfunction "2_2") (pintype "passive"))
      (node (ref "SPKR") (pin "1") (pinfunction "1_1") (pintype "passive"))
      (node (ref "U3") (pin "14") (pinfunction "~{RESET}_14") (pintype "bidirectional"))
      (node (ref "U3") (pin "15") (pinfunction "VCC_15") (pintype "bidirectional"))
      (node (ref "VR1") (pin "2") (pinfunction "VOUT_2") (pintype "output"))
      (node (ref "VR1") (pin "4") (pinfunction "VOUT_4") (pintype "output"))
      (node (ref "VR2") (pin "1") (pinfunction "VIN_1") (pintype "power_in"))
      (node (ref "VR2") (pin "3") (pinfunction "CE_3") (pintype "bidirectional"))
    )
    (net (code "76") (name "VCC_1") (class "Default")
      (node (ref "ACC") (pin "1") (pinfunction "1_1") (pintype "passive"))
      (node (ref "C10") (pin "1") (pinfunction "1_1") (pintype "passive"))
      (node (ref "C4") (pin "1") (pinfunction "1_1") (pintype "passive"))
      (node (ref "GTWI") (pin "1") (pinfunction "1_1") (pintype "passive"))
      (node (ref "Q12") (pin "1") (pinfunction "G_1") (pintype "bidirectional"))
      (node (ref "Q13") (pin "1") (pinfunction "G_1") (pintype "bidirectional"))
      (node (ref "Q14") (pin "1") (pinfunction "G_1") (pintype "bidirectional"))
      (node (ref "Q4") (pin "1") (pinfunction "G_1") (pintype "bidirectional"))
      (node (ref "Q5") (pin "1") (pinfunction "G_1") (pintype "bidirectional"))
      (node (ref "R12") (pin "2") (pinfunction "2_2") (pintype "passive"))
      (node (ref "R16") (pin "2") (pinfunction "2_2") (pintype "passive"))
      (node (ref "R19") (pin "1") (pinfunction "1_1") (pintype "passive"))
      (node (ref "R5") (pin "2") (pinfunction "2_2") (pintype "passive"))
      (node (ref "R8") (pin "2") (pinfunction "2_2") (pintype "passive"))
      (node (ref "U2") (pin "3V3") (pinfunction "VCC_3V3") (pintype "power_in"))
      (node (ref "VR2") (pin "5") (pinfunction "VOUT_5") (pintype "power_in"))
    )
    (net (code "77") (name "unconnected-(CPU-(A8)PC0-Pad53)") (class "Default")
      (node (ref "CPU") (pin "53") (pinfunction "(A8)PC0_53") (pintype "bidirectional"))
    )
    (net (code "78") (name "unconnected-(CPU-(A9)PC1-Pad54)") (class "Default")
      (node (ref "CPU") (pin "54") (pinfunction "(A9)PC1_54") (pintype "bidirectional"))
    )
    (net (code "79") (name "unconnected-(CPU-(A10)PC2-Pad55)") (class "Default")
      (node (ref "CPU") (pin "55") (pinfunction "(A10)PC2_55") (pintype "bidirectional"))
    )
    (net (code "80") (name "unconnected-(CPU-(A11)PC3-Pad56)") (class "Default")
      (node (ref "CPU") (pin "56") (pinfunction "(A11)PC3_56") (pintype "bidirectional"))
    )
    (net (code "81") (name "unconnected-(CPU-(A12)PC4-Pad57)") (class "Default")
      (node (ref "CPU") (pin "57") (pinfunction "(A12)PC4_57") (pintype "bidirectional"))
    )
    (net (code "82") (name "unconnected-(CPU-(A13)PC5-Pad58)") (class "Default")
      (node (ref "CPU") (pin "58") (pinfunction "(A13)PC5_58") (pintype "bidirectional"))
    )
    (net (code "83") (name "unconnected-(CPU-(CLKO{slash}ICP3{slash}INT7)PE7-Pad9)") (class "Default")
      (node (ref "CPU") (pin "9") (pinfunction "(CLKO/ICP3/INT7)PE7_9") (pintype "bidirectional"))
    )
    (net (code "84") (name "unconnected-(CPU-(ICP1)PD4-Pad47)") (class "Default")
      (node (ref "CPU") (pin "47") (pinfunction "(ICP1)PD4_47") (pintype "bidirectional"))
    )
    (net (code "85") (name "unconnected-(CPU-(OC0A{slash}OC1C{slash}PCINT7)PB7-Pad26)") (class "Default")
      (node (ref "CPU") (pin "26") (pinfunction "(OC0A/OC1C/PCINT7)PB7_26") (pintype "bidirectional"))
    )
    (net (code "86") (name "unconnected-(CPU-(OC1A{slash}PCINT5)PB5-Pad24)") (class "Default")
      (node (ref "CPU") (pin "24") (pinfunction "(OC1A/PCINT5)PB5_24") (pintype "bidirectional"))
    )
    (net (code "87") (name "unconnected-(CPU-(OC1B{slash}PCINT6)PB6-Pad25)") (class "Default")
      (node (ref "CPU") (pin "25") (pinfunction "(OC1B/PCINT6)PB6_25") (pintype "bidirectional"))
    )
    (net (code "88") (name "unconnected-(CPU-(OC3B{slash}INT4)PE4-Pad6)") (class "Default")
      (node (ref "CPU") (pin "6") (pinfunction "(OC3B/INT4)PE4_6") (pintype "bidirectional"))
    )
    (net (code "89") (name "unconnected-(CPU-(OC3C{slash}INT5)PE5-Pad7)") (class "Default")
      (node (ref "CPU") (pin "7") (pinfunction "(OC3C/INT5)PE5_7") (pintype "bidirectional"))
    )
    (net (code "90") (name "unconnected-(CPU-(RD)PG1-Pad52)") (class "Default")
      (node (ref "CPU") (pin "52") (pinfunction "(RD)PG1_52") (pintype "bidirectional"))
    )
    (net (code "91") (name "unconnected-(CPU-(SS{slash}PCINT0)PB0-Pad19)") (class "Default")
      (node (ref "CPU") (pin "19") (pinfunction "(SS/PCINT0)PB0_19") (pintype "bidirectional"))
    )
    (net (code "92") (name "unconnected-(CPU-(T0)PD7-Pad50)") (class "Default")
      (node (ref "CPU") (pin "50") (pinfunction "(T0)PD7_50") (pintype "bidirectional"))
    )
    (net (code "93") (name "unconnected-(CPU-(T1)PD6-Pad49)") (class "Default")
      (node (ref "CPU") (pin "49") (pinfunction "(T1)PD6_49") (pintype "bidirectional"))
    )
    (net (code "94") (name "unconnected-(CPU-(T3{slash}INT6)PE6-Pad8)") (class "Default")
      (node (ref "CPU") (pin "8") (pinfunction "(T3/INT6)PE6_8") (pintype "bidirectional"))
    )
    (net (code "95") (name "unconnected-(CPU-(TOSC1)PG4-Pad29)") (class "Default")
      (node (ref "CPU") (pin "29") (pinfunction "(TOSC1)PG4_29") (pintype "bidirectional"))
    )
    (net (code "96") (name "unconnected-(CPU-(TOSC2)PG3-Pad28)") (class "Default")
      (node (ref "CPU") (pin "28") (pinfunction "(TOSC2)PG3_28") (pintype "bidirectional"))
    )
    (net (code "97") (name "unconnected-(CPU-(WR)PG0-Pad51)") (class "Default")
      (node (ref "CPU") (pin "51") (pinfunction "(WR)PG0_51") (pintype "bidirectional"))
    )
    (net (code "98") (name "unconnected-(CPU-(XCK1)PD5-Pad48)") (class "Default")
      (node (ref "CPU") (pin "48") (pinfunction "(XCK1)PD5_48") (pintype "bidirectional"))
    )
    (net (code "99") (name "unconnected-(CPU-PH2(XCK2)-Pad14)") (class "Default")
      (node (ref "CPU") (pin "14") (pinfunction "PH2(XCK2)_14") (pintype "bidirectional"))
    )
    (net (code "100") (name "unconnected-(CPU-PH3(OC4A)-Pad15)") (class "Default")
      (node (ref "CPU") (pin "15") (pinfunction "PH3(OC4A)_15") (pintype "bidirectional"))
    )
    (net (code "101") (name "unconnected-(CPU-PH4(OC4B)-Pad16)") (class "Default")
      (node (ref "CPU") (pin "16") (pinfunction "PH4(OC4B)_16") (pintype "bidirectional"))
    )
    (net (code "102") (name "unconnected-(CPU-PH5(OC4C)-Pad17)") (class "Default")
      (node (ref "CPU") (pin "17") (pinfunction "PH5(OC4C)_17") (pintype "bidirectional"))
    )
    (net (code "103") (name "unconnected-(CPU-PH6(OC2B)-Pad18)") (class "Default")
      (node (ref "CPU") (pin "18") (pinfunction "PH6(OC2B)_18") (pintype "bidirectional"))
    )
    (net (code "104") (name "unconnected-(CPU-PH7(T4)-Pad27)") (class "Default")
      (node (ref "CPU") (pin "27") (pinfunction "PH7(T4)_27") (pintype "bidirectional"))
    )
    (net (code "105") (name "unconnected-(CPU-PJ0(RXD3{slash}PCINT9)-Pad63)") (class "Default")
      (node (ref "CPU") (pin "63") (pinfunction "PJ0(RXD3/PCINT9)_63") (pintype "bidirectional"))
    )
    (net (code "106") (name "unconnected-(CPU-PJ1(TXD3{slash}PCINT10)-Pad64)") (class "Default")
      (node (ref "CPU") (pin "64") (pinfunction "PJ1(TXD3/PCINT10)_64") (pintype "bidirectional"))
    )
    (net (code "107") (name "unconnected-(CPU-PJ2(XCK3{slash}PCINT11)-Pad65)") (class "Default")
      (node (ref "CPU") (pin "65") (pinfunction "PJ2(XCK3/PCINT11)_65") (pintype "bidirectional"))
    )
    (net (code "108") (name "unconnected-(CPU-PJ3(PCINT12)-Pad66)") (class "Default")
      (node (ref "CPU") (pin "66") (pinfunction "PJ3(PCINT12)_66") (pintype "bidirectional"))
    )
    (net (code "109") (name "unconnected-(CPU-PJ4(PCINT13)-Pad67)") (class "Default")
      (node (ref "CPU") (pin "67") (pinfunction "PJ4(PCINT13)_67") (pintype "bidirectional"))
    )
    (net (code "110") (name "unconnected-(CPU-PJ5(PCINT14)-Pad68)") (class "Default")
      (node (ref "CPU") (pin "68") (pinfunction "PJ5(PCINT14)_68") (pintype "bidirectional"))
    )
    (net (code "111") (name "unconnected-(CPU-PJ6(PCINT15)-Pad69)") (class "Default")
      (node (ref "CPU") (pin "69") (pinfunction "PJ6(PCINT15)_69") (pintype "bidirectional"))
    )
    (net (code "112") (name "unconnected-(CPU-PJ7-Pad79)") (class "Default")
      (node (ref "CPU") (pin "79") (pinfunction "PJ7_79") (pintype "bidirectional"))
    )
    (net (code "113") (name "unconnected-(CPU-PK1(ADC9{slash}PCINT17)-Pad88)") (class "Default")
      (node (ref "CPU") (pin "88") (pinfunction "PK1(ADC9/PCINT17)_88") (pintype "bidirectional"))
    )
    (net (code "114") (name "unconnected-(CPU-PK2(ADC10{slash}PCINT18)-Pad87)") (class "Default")
      (node (ref "CPU") (pin "87") (pinfunction "PK2(ADC10/PCINT18)_87") (pintype "bidirectional"))
    )
    (net (code "115") (name "unconnected-(CPU-PK3(ADC11{slash}PCINT19)-Pad86)") (class "Default")
      (node (ref "CPU") (pin "86") (pinfunction "PK3(ADC11/PCINT19)_86") (pintype "bidirectional"))
    )
    (net (code "116") (name "unconnected-(CPU-PK4(ADC12{slash}PCINT20)-Pad85)") (class "Default")
      (node (ref "CPU") (pin "85") (pinfunction "PK4(ADC12/PCINT20)_85") (pintype "bidirectional"))
    )
    (net (code "117") (name "unconnected-(CPU-PK5(ADC13{slash}PCINT21)-Pad84)") (class "Default")
      (node (ref "CPU") (pin "84") (pinfunction "PK5(ADC13/PCINT21)_84") (pintype "bidirectional"))
    )
    (net (code "118") (name "unconnected-(CPU-PK6(ADC14{slash}PCINT22)-Pad83)") (class "Default")
      (node (ref "CPU") (pin "83") (pinfunction "PK6(ADC14/PCINT22)_83") (pintype "bidirectional"))
    )
    (net (code "119") (name "unconnected-(CPU-PL2(T5)-Pad37)") (class "Default")
      (node (ref "CPU") (pin "37") (pinfunction "PL2(T5)_37") (pintype "bidirectional"))
    )
    (net (code "120") (name "unconnected-(CPU-PL6-Pad41)") (class "Default")
      (node (ref "CPU") (pin "41") (pinfunction "PL6_41") (pintype "bidirectional"))
    )
    (net (code "121") (name "unconnected-(CPU-PL7-Pad42)") (class "Default")
      (node (ref "CPU") (pin "42") (pinfunction "PL7_42") (pintype "bidirectional"))
    )
    (net (code "122") (name "unconnected-(J1-PadID)") (class "Default")
      (node (ref "J1") (pin "ID") (pinfunction "ID_ID") (pintype "bidirectional"))
    )
    (net (code "123") (name "unconnected-(U2-PadIO0)") (class "Default")
      (node (ref "U2") (pin "IO0") (pinfunction "IO0_IO0") (pintype "bidirectional"))
    )
    (net (code "124") (name "unconnected-(U2-PadIO2)") (class "Default")
      (node (ref "U2") (pin "IO2") (pinfunction "IO2_IO2") (pintype "bidirectional"))
    )
    (net (code "125") (name "unconnected-(U2-PadIO4)") (class "Default")
      (node (ref "U2") (pin "IO4") (pinfunction "IO4_IO4") (pintype "bidirectional"))
    )
    (net (code "126") (name "unconnected-(U2-PadIO5)") (class "Default")
      (node (ref "U2") (pin "IO5") (pinfunction "IO5_IO5") (pintype "bidirectional"))
    )
    (net (code "127") (name "unconnected-(U2-PadIO12)") (class "Default")
      (node (ref "U2") (pin "IO12") (pinfunction "IO12_IO12") (pintype "bidirectional"))
    )
    (net (code "128") (name "unconnected-(U2-PadIO13)") (class "Default")
      (node (ref "U2") (pin "IO13") (pinfunction "IO13_IO13") (pintype "bidirectional"))
    )
    (net (code "129") (name "unconnected-(U2-PadIO14)") (class "Default")
      (node (ref "U2") (pin "IO14") (pinfunction "IO14_IO14") (pintype "bidirectional"))
    )
    (net (code "130") (name "unconnected-(U2-PadIO15)") (class "Default")
      (node (ref "U2") (pin "IO15") (pinfunction "IO15_IO15") (pintype "bidirectional"))
    )
    (net (code "131") (name "unconnected-(U2-PadIO16)") (class "Default")
      (node (ref "U2") (pin "IO16") (pinfunction "IO16_IO16") (pintype "bidirectional"))
    )
    (net (code "132") (name "unconnected-(U2-PadTOUT)") (class "Default")
      (node (ref "U2") (pin "TOUT") (pinfunction "TOUT_TOUT") (pintype "bidirectional"))
    )
    (net (code "133") (name "unconnected-(U3-CBUS2-Pad10)") (class "Default")
      (node (ref "U3") (pin "10") (pinfunction "CBUS2_10") (pintype "bidirectional"))
    )
    (net (code "134") (name "unconnected-(U3-~{CTS}-Pad9)") (class "Default")
      (node (ref "U3") (pin "9") (pinfunction "~{CTS}_9") (pintype "bidirectional"))
    )
    (net (code "135") (name "unconnected-(U3-~{DCD}-Pad8)") (class "Default")
      (node (ref "U3") (pin "8") (pinfunction "~{DCD}_8") (pintype "bidirectional"))
    )
    (net (code "136") (name "unconnected-(U3-~{DSR}-Pad7)") (class "Default")
      (node (ref "U3") (pin "7") (pinfunction "~{DSR}_7") (pintype "bidirectional"))
    )
    (net (code "137") (name "unconnected-(U3-~{RI}-Pad5)") (class "Default")
      (node (ref "U3") (pin "5") (pinfunction "~{RI}_5") (pintype "bidirectional"))
    )
    (net (code "138") (name "unconnected-(U3-~{RTS}-Pad2)") (class "Default")
      (node (ref "U3") (pin "2") (pinfunction "~{RTS}_2") (pintype "bidirectional"))
    )
  )
)
